# schematic.net
KiCad netlist of a schematic drawn in EAGLE
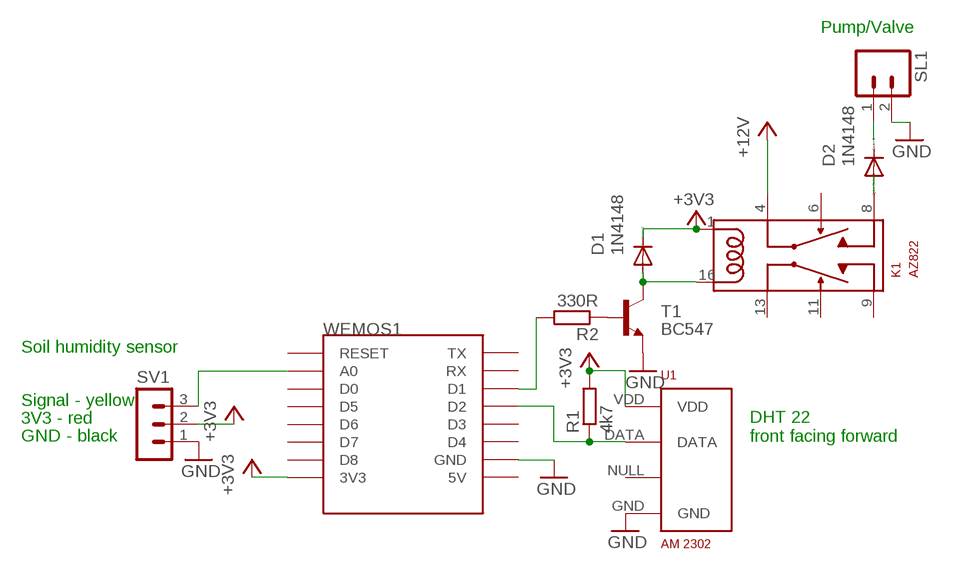
[diagram p0: schematic, sheet 1]

(export (version "E")
  (design (tool "Eeschema 10.0.6"))
  (components
    (comp (ref "D1")
      (value "1N4148")
      (footprint "eagle-import:DO35-10")
      (libsource (lib "eagle-import") (part "1N4148DO35-10"))
    )
    (comp (ref "D2")
      (value "1N4148")
      (footprint "eagle-import:DO35-10")
      (libsource (lib "eagle-import") (part "1N4148DO35-10"))
    )
    (comp (ref "K1")
      (value "AZ822")
      (footprint "eagle-import:351")
      (libsource (lib "eagle-import") (part "AZ822"))
    )
    (comp (ref "R1")
      (value "4k7")
      (footprint "eagle-import:0207_10")
      (libsource (lib "eagle-import") (part "R-EU_0207/10"))
    )
    (comp (ref "R2")
      (value "330R")
      (footprint "eagle-import:0207_10")
      (libsource (lib "eagle-import") (part "R-EU_0207/10"))
    )
    (comp (ref "SL1")
      (value "M02")
      (footprint "eagle-import:02P")
      (libsource (lib "eagle-import") (part "M02"))
    )
    (comp (ref "SV1")
      (value "MA03-1")
      (footprint "eagle-import:MA03-1")
      (libsource (lib "eagle-import") (part "MA03-1"))
    )
    (comp (ref "T1")
      (value "BC547")
      (footprint "eagle-import:TO92")
      (libsource (lib "eagle-import") (part "BC547"))
    )
    (comp (ref "U1")
      (value "AM 2302")
      (footprint "eagle-import:RHT03_DHT-22")
      (libsource (lib "eagle-import") (part "RHT03_DHT-22_AM2302"))
    )
    (comp (ref "WEMOS1")
      (value "WEMOS-D1-MINI")
      (footprint "eagle-import:WEMOS-D1-MINI")
      (libsource (lib "eagle-import") (part "WEMOS-D1-MINI"))
    )
  )
  (nets
    (net (code "1") (name "+12V") (class "Default")
      (node (ref "D1") (pin "C") (pinfunction "C_C") (pintype "passive"))
      (node (ref "K1") (pin "1") (pinfunction "1_1") (pintype "bidirectional"))
      (node (ref "K1") (pin "4") (pinfunction "4_4") (pintype "bidirectional"))
      (node (ref "R1") (pin "2") (pinfunction "2_2") (pintype "passive"))
      (node (ref "SV1") (pin "2") (pinfunction "2_2") (pintype "passive"))
      (node (ref "U1") (pin "VDD") (pinfunction "VDD_VDD") (pintype "power_in"))
      (node (ref "WEMOS1") (pin "3V3") (pinfunction "3V3_3V3") (pintype "bidirectional"))
    )
    (net (code "2") (name "GND") (class "Default")
      (node (ref "SL1") (pin "2") (pinfunction "2_2") (pintype "passive"))
      (node (ref "SV1") (pin "1") (pinfunction "1_1") (pintype "passive"))
      (node (ref "T1") (pin "1") (pinfunction "E_1") (pintype "passive"))
      (node (ref "U1") (pin "GND") (pinfunction "GND_GND") (pintype "power_in"))
      (node (ref "WEMOS1") (pin "GND") (pinfunction "GND_GND") (pintype "bidirectional"))
    )
    (net (code "3") (name "Net-(R1-Pad1)") (class "Default")
      (node (ref "R1") (pin "1") (pinfunction "1_1") (pintype "passive"))
      (node (ref "U1") (pin "DATA") (pinfunction "DATA_DATA") (pintype "bidirectional"))
      (node (ref "WEMOS1") (pin "D2") (pinfunction "D2_D2") (pintype "bidirectional"))
    )
    (net (code "4") (name "Net-(R2-Pad2)") (class "Default")
      (node (ref "R2") (pin "2") (pinfunction "2_2") (pintype "passive"))
      (node (ref "WEMOS1") (pin "D1") (pinfunction "D1_D1") (pintype "bidirectional"))
    )
    (net (code "5") (name "Net-(SV1-Pad3)") (class "Default")
      (node (ref "SV1") (pin "3") (pinfunction "3_3") (pintype "passive"))
      (node (ref "WEMOS1") (pin "A0") (pinfunction "A0_A0") (pintype "bidirectional"))
    )
    (net (code "6") (name "Net-(T1-B)") (class "Default")
      (node (ref "R2") (pin "1") (pinfunction "1_1") (pintype "passive"))
      (node (ref "T1") (pin "2") (pinfunction "B_2") (pintype "passive"))
    )
    (net (code "7") (name "Net-(T1-C)") (class "Default")
      (node (ref "D1") (pin "A") (pinfunction "A_A") (pintype "passive"))
      (node (ref "K1") (pin "16") (pinfunction "16_16") (pintype "bidirectional"))
      (node (ref "T1") (pin "3") (pinfunction "C_3") (pintype "passive"))
    )
    (net (code "8") (name "unconnected-(D2-PadA)") (class "Default")
      (node (ref "D2") (pin "A") (pinfunction "A_A") (pintype "passive"))
    )
    (net (code "9") (name "unconnected-(D2-PadC)") (class "Default")
      (node (ref "D2") (pin "C") (pinfunction "C_C") (pintype "passive"))
    )
    (net (code "10") (name "unconnected-(K1-Pad6)") (class "Default")
      (node (ref "K1") (pin "6") (pinfunction "6_6") (pintype "bidirectional"))
    )
    (net (code "11") (name "unconnected-(K1-Pad8)") (class "Default")
      (node (ref "K1") (pin "8") (pinfunction "8_8") (pintype "bidirectional"))
    )
    (net (code "12") (name "unconnected-(K1-Pad9)") (class "Default")
      (node (ref "K1") (pin "9") (pinfunction "9_9") (pintype "bidirectional"))
    )
    (net (code "13") (name "unconnected-(K1-Pad11)") (class "Default")
      (node (ref "K1") (pin "11") (pinfunction "11_11") (pintype "bidirectional"))
    )
    (net (code "14") (name "unconnected-(K1-Pad13)") (class "Default")
      (node (ref "K1") (pin "13") (pinfunction "13_13") (pintype "bidirectional"))
    )
    (net (code "15") (name "unconnected-(SL1-Pad1)") (class "Default")
      (node (ref "SL1") (pin "1") (pinfunction "1_1") (pintype "passive"))
    )
    (net (code "16") (name "unconnected-(U1-PadNULL)") (class "Default")
      (node (ref "U1") (pin "NULL") (pinfunction "NULL_NULL") (pintype "no_connect"))
    )
    (net (code "17") (name "unconnected-(WEMOS1-Pad5V)") (class "Default")
      (node (ref "WEMOS1") (pin "5V") (pinfunction "5V_5V") (pintype "bidirectional"))
    )
    (net (code "18") (name "unconnected-(WEMOS1-PadD0)") (class "Default")
      (node (ref "WEMOS1") (pin "D0") (pinfunction "D0_D0") (pintype "bidirectional"))
    )
    (net (code "19") (name "unconnected-(WEMOS1-PadD3)") (class "Default")
      (node (ref "WEMOS1") (pin "D3") (pinfunction "D3_D3") (pintype "bidirectional"))
    )
    (net (code "20") (name "unconnected-(WEMOS1-PadD4)") (class "Default")
      (node (ref "WEMOS1") (pin "D4") (pinfunction "D4_D4") (pintype "bidirectional"))
    )
    (net (code "21") (name "unconnected-(WEMOS1-PadD5)") (class "Default")
      (node (ref "WEMOS1") (pin "D5") (pinfunction "D5_D5") (pintype "bidirectional"))
    )
    (net (code "22") (name "unconnected-(WEMOS1-PadD6)") (class "Default")
      (node (ref "WEMOS1") (pin "D6") (pinfunction "D6_D6") (pintype "bidirectional"))
    )
    (net (code "23") (name "unconnected-(WEMOS1-PadD7)") (class "Default")
      (node (ref "WEMOS1") (pin "D7") (pinfunction "D7_D7") (pintype "bidirectional"))
    )
    (net (code "24") (name "unconnected-(WEMOS1-PadD8)") (class "Default")
      (node (ref "WEMOS1") (pin "D8") (pinfunction "D8_D8") (pintype "bidirectional"))
    )
    (net (code "25") (name "unconnected-(WEMOS1-PadRESET)") (class "Default")
      (node (ref "WEMOS1") (pin "RESET") (pinfunction "RESET_RESET") (pintype "bidirectional"))
    )
    (net (code "26") (name "unconnected-(WEMOS1-PadRX)") (class "Default")
      (node (ref "WEMOS1") (pin "RX") (pinfunction "RX_RX") (pintype "bidirectional"))
    )
    (net (code "27") (name "unconnected-(WEMOS1-PadTX)") (class "Default")
      (node (ref "WEMOS1") (pin "TX") (pinfunction "TX_TX") (pintype "bidirectional"))
    )
  )
)
